# FPGA_MGT.net
KiCad netlist of a schematic drawn in Altium Designer
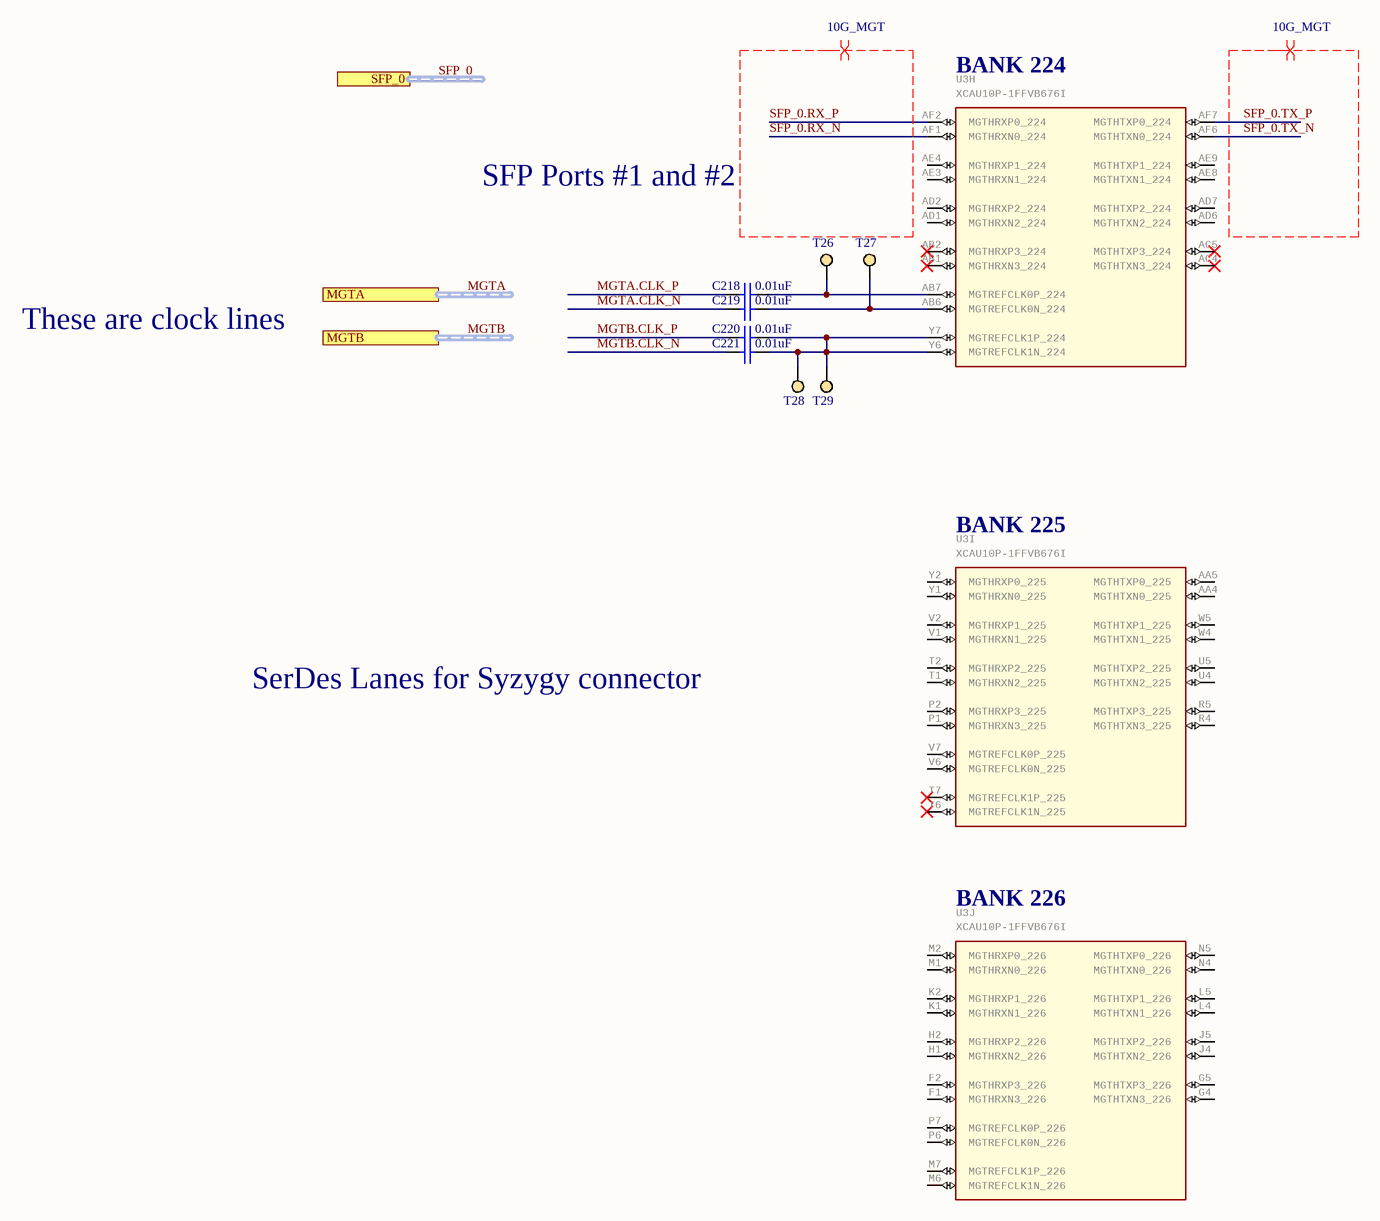
[diagram p0: FPGA_MGT.SchDoc]

(export (version "E")
  (design (tool "Eeschema 10.0.6"))
  (components
    (comp (ref "C218")
      (value "0.01uF")
      (footprint "CAPC1005X55USR")
      (description "CAP CER 10000PF 50V X7R 0402")
      (fields
        (field (name "MANUFACTURER PART NUMBER") "GCM155R71H103KA55D")
        (field (name "MANUFACTURER") "Murata Electronics")
      )
      (libsource (lib "Radar FPGA RF") (part "CAP CER 0.01uF 50V X7R 0402"))
    )
    (comp (ref "C219")
      (value "0.01uF")
      (footprint "CAPC1005X55USR")
      (description "CAP CER 10000PF 50V X7R 0402")
      (fields
        (field (name "MANUFACTURER PART NUMBER") "GCM155R71H103KA55D")
        (field (name "MANUFACTURER") "Murata Electronics")
      )
      (libsource (lib "Radar FPGA RF") (part "CAP CER 0.01uF 50V X7R 0402"))
    )
    (comp (ref "C220")
      (value "0.01uF")
      (footprint "CAPC1005X55USR")
      (description "CAP CER 10000PF 50V X7R 0402")
      (fields
        (field (name "MANUFACTURER PART NUMBER") "GCM155R71H103KA55D")
        (field (name "MANUFACTURER") "Murata Electronics")
      )
      (libsource (lib "Radar FPGA RF") (part "CAP CER 0.01uF 50V X7R 0402"))
    )
    (comp (ref "C221")
      (value "0.01uF")
      (footprint "CAPC1005X55USR")
      (description "CAP CER 10000PF 50V X7R 0402")
      (fields
        (field (name "MANUFACTURER PART NUMBER") "GCM155R71H103KA55D")
        (field (name "MANUFACTURER") "Murata Electronics")
      )
      (libsource (lib "Radar FPGA RF") (part "CAP CER 0.01uF 50V X7R 0402"))
    )
    (comp (ref "T26")
      (value "TP_S")
      (footprint "TP_SM_1MM")
      (description "test point")
      (libsource (lib "Radar FPGA RF") (part "Test point PAD"))
    )
    (comp (ref "T27")
      (value "TP_S")
      (footprint "TP_SM_1MM")
      (description "test point")
      (libsource (lib "Radar FPGA RF") (part "Test point PAD"))
    )
    (comp (ref "T28")
      (value "TP_S")
      (footprint "TP_SM_1MM")
      (description "test point")
      (libsource (lib "Radar FPGA RF") (part "Test point PAD"))
    )
    (comp (ref "T29")
      (value "TP_S")
      (footprint "TP_SM_1MM")
      (description "test point")
      (libsource (lib "Radar FPGA RF") (part "Test point PAD"))
    )
    (comp (ref "U3")
      (value "XCAU10P-1FFVB676I")
      (footprint "676-FCBGA (27x27)")
      (description "IC FPGA ARTIXUP 676BGA")
      (fields (field (name "MANUFACTURER") "AMD Xilinx"))
      (libsource (lib "LL") (part "XCAU10P-1FFVB676I"))
    )
  )
  (nets
    (net (code "4") (name "/MGTA.CLK_N") (class "Default")
      (node (ref "C219") (pin "1") (pinfunction "1_1") (pintype "passive"))
    )
    (net (code "5") (name "/MGTA.CLK_P") (class "Default")
      (node (ref "C218") (pin "1") (pinfunction "1_1") (pintype "passive"))
    )
    (net (code "6") (name "/MGTB.CLK_N") (class "Default")
      (node (ref "C221") (pin "1") (pinfunction "1_1") (pintype "passive"))
    )
    (net (code "7") (name "/MGTB.CLK_P") (class "Default")
      (node (ref "C220") (pin "1") (pinfunction "1_1") (pintype "passive"))
    )
    (net (code "8") (name "/SFP_0.RX_N") (class "Default")
      (node (ref "U3") (pin "AF1") (pinfunction "MGTHRXN0_224_AF1") (pintype "bidirectional"))
    )
    (net (code "9") (name "/SFP_0.RX_P") (class "Default")
      (node (ref "U3") (pin "AF2") (pinfunction "MGTHRXP0_224_AF2") (pintype "bidirectional"))
    )
    (net (code "10") (name "/SFP_0.TX_N") (class "Default")
      (node (ref "U3") (pin "AF6") (pinfunction "MGTHTXN0_224_AF6") (pintype "bidirectional"))
    )
    (net (code "11") (name "/SFP_0.TX_P") (class "Default")
      (node (ref "U3") (pin "AF7") (pinfunction "MGTHTXP0_224_AF7") (pintype "bidirectional"))
    )
    (net (code "15") (name "Net-(U3H-MGTREFCLK0N_224)") (class "Default")
      (node (ref "C219") (pin "2") (pinfunction "2_2") (pintype "passive"))
      (node (ref "T27") (pin "1") (pintype "passive"))
      (node (ref "U3") (pin "AB6") (pinfunction "MGTREFCLK0N_224_AB6") (pintype "bidirectional"))
    )
    (net (code "16") (name "Net-(U3H-MGTREFCLK0P_224)") (class "Default")
      (node (ref "C218") (pin "2") (pinfunction "2_2") (pintype "passive"))
      (node (ref "T26") (pin "1") (pintype "passive"))
      (node (ref "U3") (pin "AB7") (pinfunction "MGTREFCLK0P_224_AB7") (pintype "bidirectional"))
    )
    (net (code "17") (name "Net-(U3H-MGTREFCLK1N_224)") (class "Default")
      (node (ref "C220") (pin "2") (pinfunction "2_2") (pintype "passive"))
      (node (ref "C221") (pin "2") (pinfunction "2_2") (pintype "passive"))
      (node (ref "T28") (pin "1") (pintype "passive"))
      (node (ref "T29") (pin "1") (pintype "passive"))
      (node (ref "U3") (pin "Y6") (pinfunction "MGTREFCLK1N_224_Y6") (pintype "bidirectional"))
      (node (ref "U3") (pin "Y7") (pinfunction "MGTREFCLK1P_224_Y7") (pintype "bidirectional"))
    )
    (net (code "18") (name "unconnected-(U3H-MGTHRXN1_224-PadAE3)") (class "Default")
      (node (ref "U3") (pin "AE3") (pinfunction "MGTHRXN1_224_AE3") (pintype "bidirectional"))
    )
    (net (code "19") (name "unconnected-(U3H-MGTHRXN2_224-PadAD1)") (class "Default")
      (node (ref "U3") (pin "AD1") (pinfunction "MGTHRXN2_224_AD1") (pintype "bidirectional"))
    )
    (net (code "20") (name "unconnected-(U3H-MGTHRXN3_224-PadAB1)") (class "Default")
      (node (ref "U3") (pin "AB1") (pinfunction "MGTHRXN3_224_AB1") (pintype "bidirectional+no_connect"))
    )
    (net (code "21") (name "unconnected-(U3H-MGTHRXP1_224-PadAE4)") (class "Default")
      (node (ref "U3") (pin "AE4") (pinfunction "MGTHRXP1_224_AE4") (pintype "bidirectional"))
    )
    (net (code "22") (name "unconnected-(U3H-MGTHRXP2_224-PadAD2)") (class "Default")
      (node (ref "U3") (pin "AD2") (pinfunction "MGTHRXP2_224_AD2") (pintype "bidirectional"))
    )
    (net (code "23") (name "unconnected-(U3H-MGTHRXP3_224-PadAB2)") (class "Default")
      (node (ref "U3") (pin "AB2") (pinfunction "MGTHRXP3_224_AB2") (pintype "bidirectional+no_connect"))
    )
    (net (code "24") (name "unconnected-(U3H-MGTHTXN1_224-PadAE8)") (class "Default")
      (node (ref "U3") (pin "AE8") (pinfunction "MGTHTXN1_224_AE8") (pintype "bidirectional"))
    )
    (net (code "25") (name "unconnected-(U3H-MGTHTXN2_224-PadAD6)") (class "Default")
      (node (ref "U3") (pin "AD6") (pinfunction "MGTHTXN2_224_AD6") (pintype "bidirectional"))
    )
    (net (code "26") (name "unconnected-(U3H-MGTHTXN3_224-PadAC4)") (class "Default")
      (node (ref "U3") (pin "AC4") (pinfunction "MGTHTXN3_224_AC4") (pintype "bidirectional+no_connect"))
    )
    (net (code "27") (name "unconnected-(U3H-MGTHTXP1_224-PadAE9)") (class "Default")
      (node (ref "U3") (pin "AE9") (pinfunction "MGTHTXP1_224_AE9") (pintype "bidirectional"))
    )
    (net (code "28") (name "unconnected-(U3H-MGTHTXP2_224-PadAD7)") (class "Default")
      (node (ref "U3") (pin "AD7") (pinfunction "MGTHTXP2_224_AD7") (pintype "bidirectional"))
    )
    (net (code "29") (name "unconnected-(U3H-MGTHTXP3_224-PadAC5)") (class "Default")
      (node (ref "U3") (pin "AC5") (pinfunction "MGTHTXP3_224_AC5") (pintype "bidirectional+no_connect"))
    )
    (net (code "30") (name "unconnected-(U3I-MGTHRXN0_225-PadY1)") (class "Default")
      (node (ref "U3") (pin "Y1") (pinfunction "MGTHRXN0_225_Y1") (pintype "bidirectional"))
    )
    (net (code "31") (name "unconnected-(U3I-MGTHRXN1_225-PadV1)") (class "Default")
      (node (ref "U3") (pin "V1") (pinfunction "MGTHRXN1_225_V1") (pintype "bidirectional"))
    )
    (net (code "32") (name "unconnected-(U3I-MGTHRXN2_225-PadT1)") (class "Default")
      (node (ref "U3") (pin "T1") (pinfunction "MGTHRXN2_225_T1") (pintype "bidirectional"))
    )
    (net (code "33") (name "unconnected-(U3I-MGTHRXN3_225-PadP1)") (class "Default")
      (node (ref "U3") (pin "P1") (pinfunction "MGTHRXN3_225_P1") (pintype "bidirectional"))
    )
    (net (code "34") (name "unconnected-(U3I-MGTHRXP0_225-PadY2)") (class "Default")
      (node (ref "U3") (pin "Y2") (pinfunction "MGTHRXP0_225_Y2") (pintype "bidirectional"))
    )
    (net (code "35") (name "unconnected-(U3I-MGTHRXP1_225-PadV2)") (class "Default")
      (node (ref "U3") (pin "V2") (pinfunction "MGTHRXP1_225_V2") (pintype "bidirectional"))
    )
    (net (code "36") (name "unconnected-(U3I-MGTHRXP2_225-PadT2)") (class "Default")
      (node (ref "U3") (pin "T2") (pinfunction "MGTHRXP2_225_T2") (pintype "bidirectional"))
    )
    (net (code "37") (name "unconnected-(U3I-MGTHRXP3_225-PadP2)") (class "Default")
      (node (ref "U3") (pin "P2") (pinfunction "MGTHRXP3_225_P2") (pintype "bidirectional"))
    )
    (net (code "38") (name "unconnected-(U3I-MGTHTXN0_225-PadAA4)") (class "Default")
      (node (ref "U3") (pin "AA4") (pinfunction "MGTHTXN0_225_AA4") (pintype "bidirectional"))
    )
    (net (code "39") (name "unconnected-(U3I-MGTHTXN1_225-PadW4)") (class "Default")
      (node (ref "U3") (pin "W4") (pinfunction "MGTHTXN1_225_W4") (pintype "bidirectional"))
    )
    (net (code "40") (name "unconnected-(U3I-MGTHTXN2_225-PadU4)") (class "Default")
      (node (ref "U3") (pin "U4") (pinfunction "MGTHTXN2_225_U4") (pintype "bidirectional"))
    )
    (net (code "41") (name "unconnected-(U3I-MGTHTXN3_225-PadR4)") (class "Default")
      (node (ref "U3") (pin "R4") (pinfunction "MGTHTXN3_225_R4") (pintype "bidirectional"))
    )
    (net (code "42") (name "unconnected-(U3I-MGTHTXP0_225-PadAA5)") (class "Default")
      (node (ref "U3") (pin "AA5") (pinfunction "MGTHTXP0_225_AA5") (pintype "bidirectional"))
    )
    (net (code "43") (name "unconnected-(U3I-MGTHTXP1_225-PadW5)") (class "Default")
      (node (ref "U3") (pin "W5") (pinfunction "MGTHTXP1_225_W5") (pintype "bidirectional"))
    )
    (net (code "44") (name "unconnected-(U3I-MGTHTXP2_225-PadU5)") (class "Default")
      (node (ref "U3") (pin "U5") (pinfunction "MGTHTXP2_225_U5") (pintype "bidirectional"))
    )
    (net (code "45") (name "unconnected-(U3I-MGTHTXP3_225-PadR5)") (class "Default")
      (node (ref "U3") (pin "R5") (pinfunction "MGTHTXP3_225_R5") (pintype "bidirectional"))
    )
    (net (code "46") (name "unconnected-(U3I-MGTREFCLK0N_225-PadV6)") (class "Default")
      (node (ref "U3") (pin "V6") (pinfunction "MGTREFCLK0N_225_V6") (pintype "bidirectional"))
    )
    (net (code "47") (name "unconnected-(U3I-MGTREFCLK0P_225-PadV7)") (class "Default")
      (node (ref "U3") (pin "V7") (pinfunction "MGTREFCLK0P_225_V7") (pintype "bidirectional"))
    )
    (net (code "48") (name "unconnected-(U3I-MGTREFCLK1N_225-PadT6)") (class "Default")
      (node (ref "U3") (pin "T6") (pinfunction "MGTREFCLK1N_225_T6") (pintype "bidirectional+no_connect"))
    )
    (net (code "49") (name "unconnected-(U3I-MGTREFCLK1P_225-PadT7)") (class "Default")
      (node (ref "U3") (pin "T7") (pinfunction "MGTREFCLK1P_225_T7") (pintype "bidirectional+no_connect"))
    )
    (net (code "50") (name "unconnected-(U3J-MGTHRXN0_226-PadM1)") (class "Default")
      (node (ref "U3") (pin "M1") (pinfunction "MGTHRXN0_226_M1") (pintype "bidirectional"))
    )
    (net (code "51") (name "unconnected-(U3J-MGTHRXN1_226-PadK1)") (class "Default")
      (node (ref "U3") (pin "K1") (pinfunction "MGTHRXN1_226_K1") (pintype "bidirectional"))
    )
    (net (code "52") (name "unconnected-(U3J-MGTHRXN2_226-PadH1)") (class "Default")
      (node (ref "U3") (pin "H1") (pinfunction "MGTHRXN2_226_H1") (pintype "bidirectional"))
    )
    (net (code "53") (name "unconnected-(U3J-MGTHRXN3_226-PadF1)") (class "Default")
      (node (ref "U3") (pin "F1") (pinfunction "MGTHRXN3_226_F1") (pintype "bidirectional"))
    )
    (net (code "54") (name "unconnected-(U3J-MGTHRXP0_226-PadM2)") (class "Default")
      (node (ref "U3") (pin "M2") (pinfunction "MGTHRXP0_226_M2") (pintype "bidirectional"))
    )
    (net (code "55") (name "unconnected-(U3J-MGTHRXP1_226-PadK2)") (class "Default")
      (node (ref "U3") (pin "K2") (pinfunction "MGTHRXP1_226_K2") (pintype "bidirectional"))
    )
    (net (code "56") (name "unconnected-(U3J-MGTHRXP2_226-PadH2)") (class "Default")
      (node (ref "U3") (pin "H2") (pinfunction "MGTHRXP2_226_H2") (pintype "bidirectional"))
    )
    (net (code "57") (name "unconnected-(U3J-MGTHRXP3_226-PadF2)") (class "Default")
      (node (ref "U3") (pin "F2") (pinfunction "MGTHRXP3_226_F2") (pintype "bidirectional"))
    )
    (net (code "58") (name "unconnected-(U3J-MGTHTXN0_226-PadN4)") (class "Default")
      (node (ref "U3") (pin "N4") (pinfunction "MGTHTXN0_226_N4") (pintype "bidirectional"))
    )
    (net (code "59") (name "unconnected-(U3J-MGTHTXN1_226-PadL4)") (class "Default")
      (node (ref "U3") (pin "L4") (pinfunction "MGTHTXN1_226_L4") (pintype "bidirectional"))
    )
    (net (code "60") (name "unconnected-(U3J-MGTHTXN2_226-PadJ4)") (class "Default")
      (node (ref "U3") (pin "J4") (pinfunction "MGTHTXN2_226_J4") (pintype "bidirectional"))
    )
    (net (code "61") (name "unconnected-(U3J-MGTHTXN3_226-PadG4)") (class "Default")
      (node (ref "U3") (pin "G4") (pinfunction "MGTHTXN3_226_G4") (pintype "bidirectional"))
    )
    (net (code "62") (name "unconnected-(U3J-MGTHTXP0_226-PadN5)") (class "Default")
      (node (ref "U3") (pin "N5") (pinfunction "MGTHTXP0_226_N5") (pintype "bidirectional"))
    )
    (net (code "63") (name "unconnected-(U3J-MGTHTXP1_226-PadL5)") (class "Default")
      (node (ref "U3") (pin "L5") (pinfunction "MGTHTXP1_226_L5") (pintype "bidirectional"))
    )
    (net (code "64") (name "unconnected-(U3J-MGTHTXP2_226-PadJ5)") (class "Default")
      (node (ref "U3") (pin "J5") (pinfunction "MGTHTXP2_226_J5") (pintype "bidirectional"))
    )
    (net (code "65") (name "unconnected-(U3J-MGTHTXP3_226-PadG5)") (class "Default")
      (node (ref "U3") (pin "G5") (pinfunction "MGTHTXP3_226_G5") (pintype "bidirectional"))
    )
    (net (code "66") (name "unconnected-(U3J-MGTREFCLK0N_226-PadP6)") (class "Default")
      (node (ref "U3") (pin "P6") (pinfunction "MGTREFCLK0N_226_P6") (pintype "bidirectional"))
    )
    (net (code "67") (name "unconnected-(U3J-MGTREFCLK0P_226-PadP7)") (class "Default")
      (node (ref "U3") (pin "P7") (pinfunction "MGTREFCLK0P_226_P7") (pintype "bidirectional"))
    )
    (net (code "68") (name "unconnected-(U3J-MGTREFCLK1N_226-PadM6)") (class "Default")
      (node (ref "U3") (pin "M6") (pinfunction "MGTREFCLK1N_226_M6") (pintype "bidirectional"))
    )
    (net (code "69") (name "unconnected-(U3J-MGTREFCLK1P_226-PadM7)") (class "Default")
      (node (ref "U3") (pin "M7") (pinfunction "MGTREFCLK1P_226_M7") (pintype "bidirectional"))
    )
  )
)
